# NIP_-3.net
KiCad netlist of a schematic drawn in Altium Designer
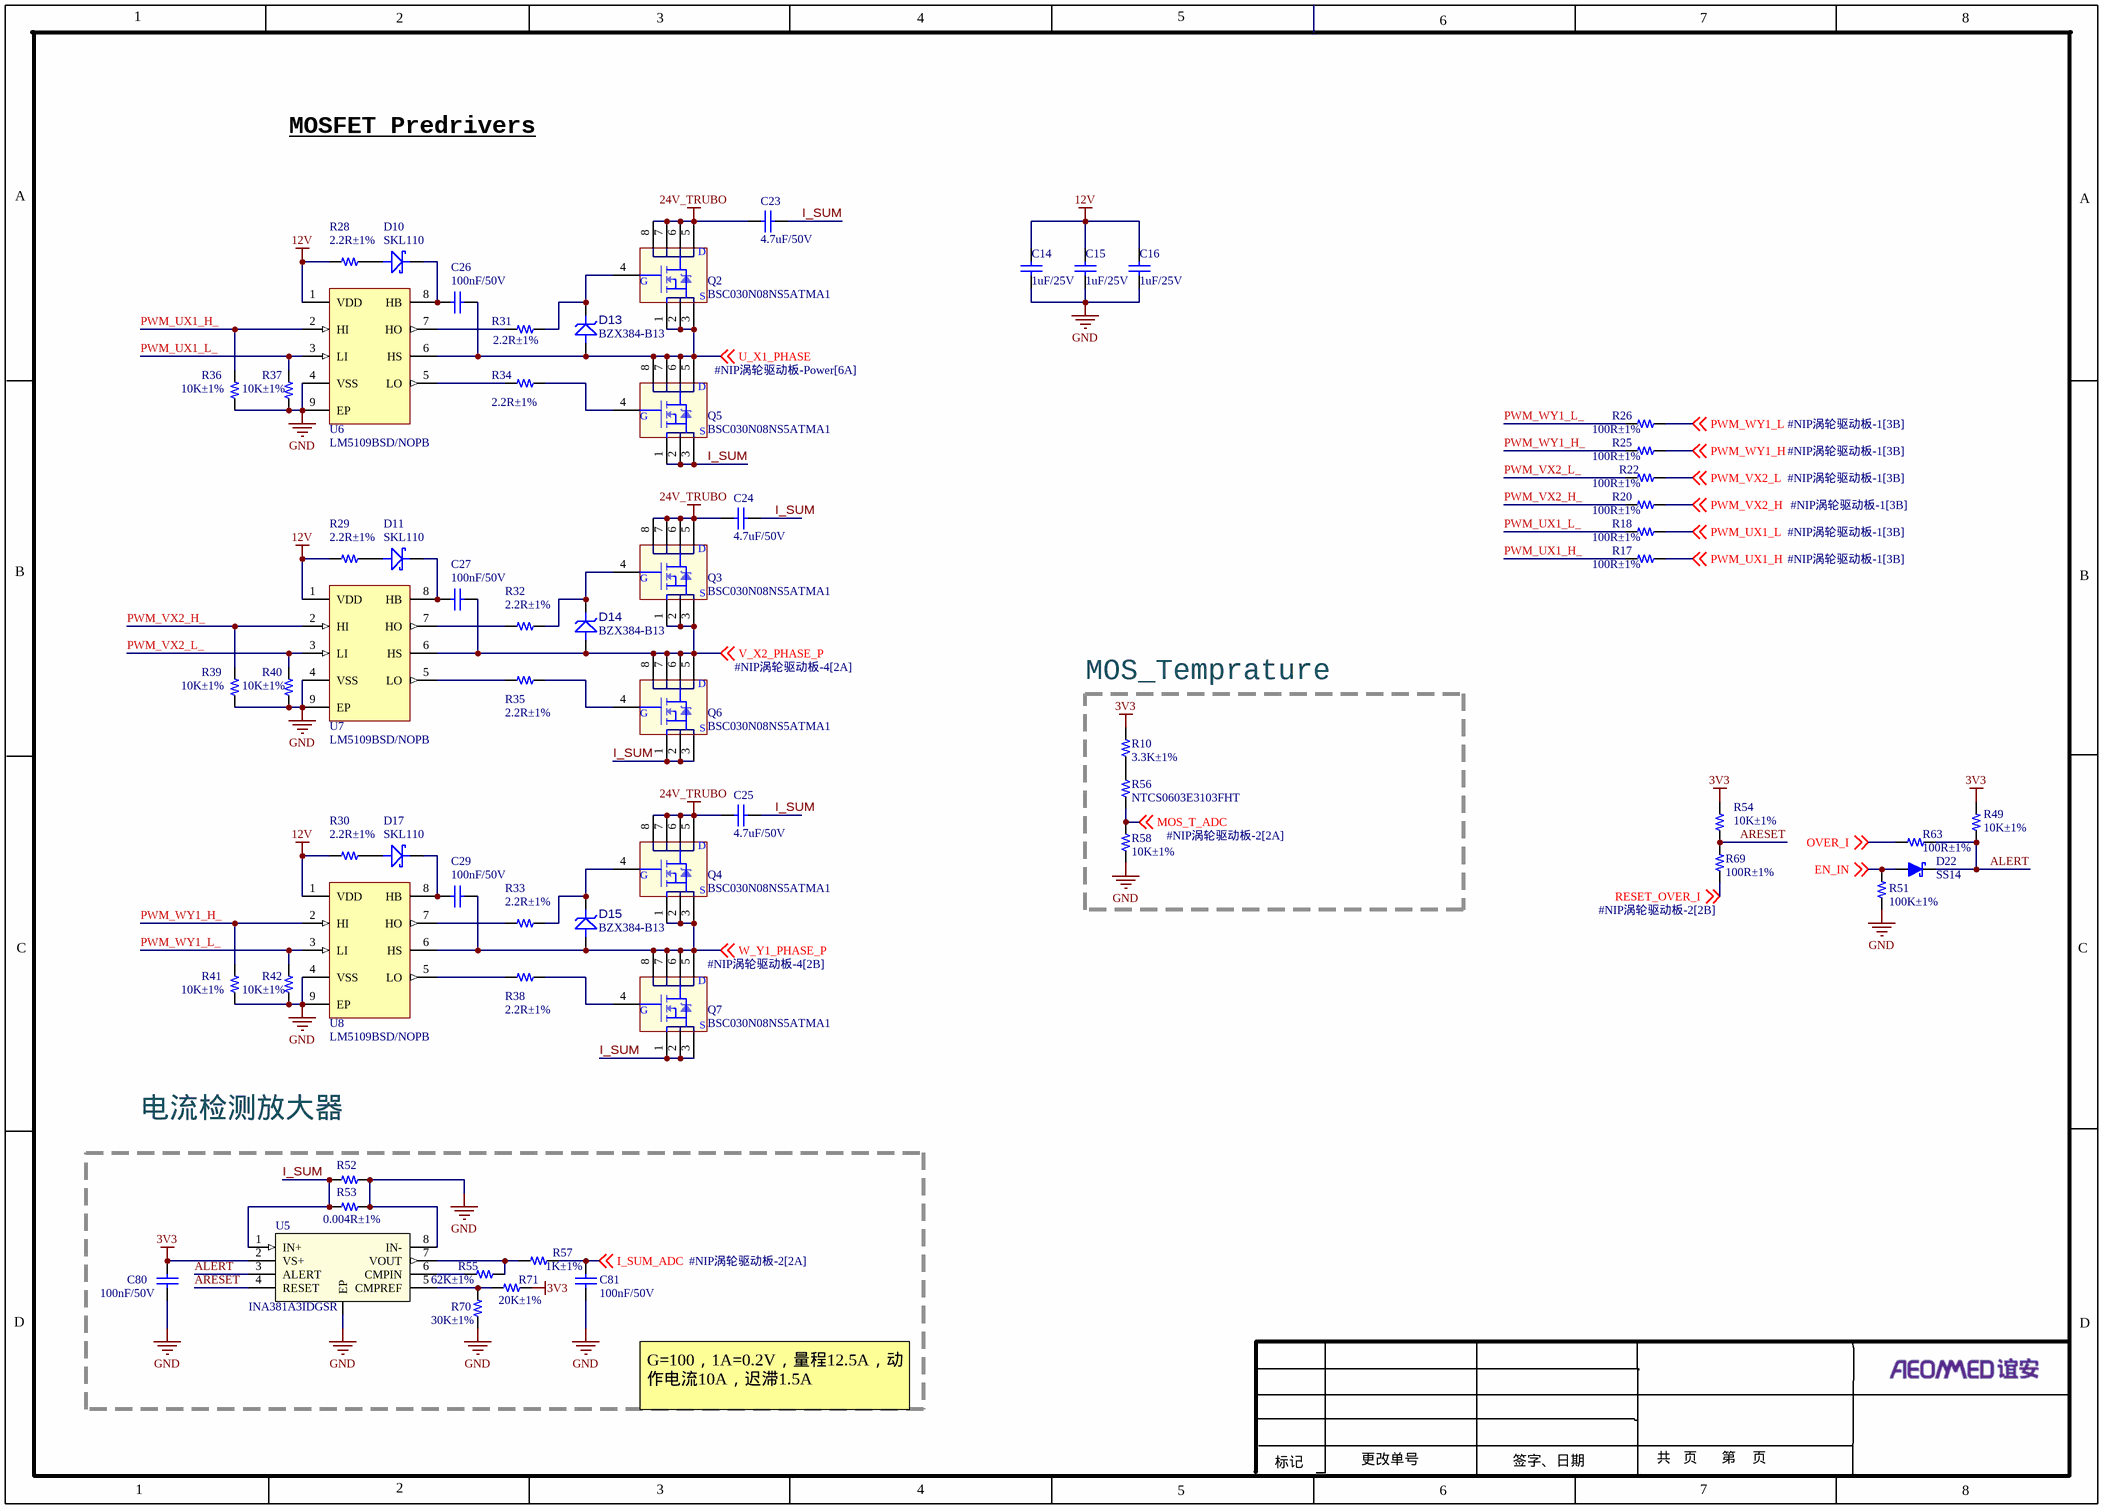
[diagram p0: #NIP涡轮驱动板-3.SchDoc]

(export (version "E")
  (design (tool "Eeschema 10.0.6"))
  (components
    (comp (ref "C14") (value "1uF/25V") (footprint "C-0805") (libsource (lib "Device") (part "C-0805")))
    (comp (ref "C15") (value "1uF/25V") (footprint "C-0805") (libsource (lib "Device") (part "C-0805")))
    (comp (ref "C16") (value "1uF/25V") (footprint "C-0805") (libsource (lib "Device") (part "C-0805")))
    (comp (ref "C23") (value "4.7uF/50V") (footprint "C-1210") (libsource (lib "Device") (part "C-1210")))
    (comp (ref "C24") (value "4.7uF/50V") (footprint "C-1210") (libsource (lib "Device") (part "C-1210")))
    (comp (ref "C25") (value "4.7uF/50V") (footprint "C-1210") (libsource (lib "Device") (part "C-1210")))
    (comp (ref "C26") (value "100nF/50V") (footprint "C-0603") (libsource (lib "Device") (part "C-0603")))
    (comp (ref "C27") (value "100nF/50V") (footprint "C-0603") (libsource (lib "Device") (part "C-0603")))
    (comp (ref "C29") (value "100nF/50V") (footprint "C-0603") (libsource (lib "Device") (part "C-0603")))
    (comp (ref "C80") (value "100nF/50V") (footprint "C0402") (libsource (lib "Device") (part "C-0603")))
    (comp (ref "C81") (value "100nF/50V") (footprint "C0402") (libsource (lib "Device") (part "C-0603")))
    (comp (ref "D10")
      (value "SKL110")
      (footprint "SODFL370X140-2N")
      (description "品牌：DIOTEC，型号：SKL110，1A，100V，ROHS")
      (fields (field (name "MANUFACTURER") "Diotec  Semiconductor"))
      (libsource (lib "altium-import") (part "root_2_DIO-SCHOTTKY_"))
    )
    (comp (ref "D11")
      (value "SKL110")
      (footprint "SODFL370X140-2N")
      (description "品牌：DIOTEC，型号：SKL110，1A，100V，ROHS")
      (fields (field (name "MANUFACTURER") "Diotec  Semiconductor"))
      (libsource (lib "altium-import") (part "root_2_DIO-SCHOTTKY_"))
    )
    (comp (ref "D13")
      (value "BZX384-B13")
      (footprint "SOD2512X100N")
      (description "品牌：NXP，型号：BZX384-B13，13V，SOD-323，ROHS")
      (fields (field (name "MANUFACTURER") "Nexperia"))
      (libsource (lib "BLDC") (part "ZENER"))
    )
    (comp (ref "D14")
      (value "BZX384-B13")
      (footprint "SOD2512X100N")
      (description "品牌：NXP，型号：BZX384-B13，13V，SOD-323，ROHS")
      (fields (field (name "MANUFACTURER") "Nexperia"))
      (libsource (lib "BLDC") (part "ZENER"))
    )
    (comp (ref "D15")
      (value "BZX384-B13")
      (footprint "SOD2512X100N")
      (description "品牌：NXP，型号：BZX384-B13，13V，SOD-323，ROHS")
      (fields (field (name "MANUFACTURER") "Nexperia"))
      (libsource (lib "BLDC") (part "ZENER"))
    )
    (comp (ref "D17")
      (value "SKL110")
      (footprint "SODFL370X140-2N")
      (description "品牌：DIOTEC，型号：SKL110，1A，100V，ROHS")
      (fields (field (name "MANUFACTURER") "Diotec  Semiconductor"))
      (libsource (lib "altium-import") (part "root_2_DIO-SCHOTTKY_"))
    )
    (comp (ref "D22")
      (value "SS14")
      (footprint "DO-214AC/SMA")
      (description "品牌：VISHAY,型号：SS14,1A,40V,ROHS")
      (libsource (lib "Device") (part "Diode- 肖特基-214AC  (SMA)"))
    )
    (comp (ref "Q2")
      (value "BSC030N08NS5ATMA1")
      (footprint "PG-TDSON-8")
      (description "品牌：INFINEON，型号： BSC027N04LSG，40V，100A，ROHS")
      (libsource (lib "IC") (part "BSC027N04LS"))
    )
    (comp (ref "Q3")
      (value "BSC030N08NS5ATMA1")
      (footprint "PG-TDSON-8")
      (description "品牌：INFINEON，型号： BSC027N04LSG，40V，100A，ROHS")
      (libsource (lib "IC") (part "BSC027N04LS"))
    )
    (comp (ref "Q4")
      (value "BSC030N08NS5ATMA1")
      (footprint "PG-TDSON-8")
      (description "品牌：INFINEON，型号： BSC027N04LSG，40V，100A，ROHS")
      (libsource (lib "IC") (part "BSC027N04LS"))
    )
    (comp (ref "Q5")
      (value "BSC030N08NS5ATMA1")
      (footprint "PG-TDSON-8")
      (description "品牌：INFINEON，型号： BSC027N04LSG，40V，100A，ROHS")
      (libsource (lib "IC") (part "BSC027N04LS"))
    )
    (comp (ref "Q6")
      (value "BSC030N08NS5ATMA1")
      (footprint "PG-TDSON-8")
      (description "品牌：INFINEON，型号： BSC027N04LSG，40V，100A，ROHS")
      (libsource (lib "IC") (part "BSC027N04LS"))
    )
    (comp (ref "Q7")
      (value "BSC030N08NS5ATMA1")
      (footprint "PG-TDSON-8")
      (description "品牌：INFINEON，型号： BSC027N04LSG，40V，100A，ROHS")
      (libsource (lib "IC") (part "BSC027N04LS"))
    )
    (comp (ref "R10") (value "3.3K±1%") (footprint "R0402") (libsource (lib "Device") (part "R-0603")))
    (comp (ref "R17") (value "100R±1%") (footprint "R0402") (libsource (lib "Device") (part "R-0603")))
    (comp (ref "R18") (value "100R±1%") (footprint "R0402") (libsource (lib "Device") (part "R-0603")))
    (comp (ref "R20") (value "100R±1%") (footprint "R0402") (libsource (lib "Device") (part "R-0603")))
    (comp (ref "R22") (value "100R±1%") (footprint "R0402") (libsource (lib "Device") (part "R-0603")))
    (comp (ref "R25") (value "100R±1%") (footprint "R0402") (libsource (lib "Device") (part "R-0603")))
    (comp (ref "R26") (value "100R±1%") (footprint "R0402") (libsource (lib "Device") (part "R-0603")))
    (comp (ref "R28") (value "2.2R±1%") (footprint "R-0603") (libsource (lib "Device") (part "R-0603")))
    (comp (ref "R29") (value "2.2R±1%") (footprint "R-0603") (libsource (lib "Device") (part "R-0603")))
    (comp (ref "R30") (value "2.2R±1%") (footprint "R-0603") (libsource (lib "Device") (part "R-0603")))
    (comp (ref "R31") (value "2.2R±1%") (footprint "R-0603") (libsource (lib "Device") (part "R-0603")))
    (comp (ref "R32") (value "2.2R±1%") (footprint "R-0603") (libsource (lib "Device") (part "R-0603")))
    (comp (ref "R33") (value "2.2R±1%") (footprint "R-0603") (libsource (lib "Device") (part "R-0603")))
    (comp (ref "R34") (value "2.2R±1%") (footprint "R-0603") (libsource (lib "Device") (part "R-0603")))
    (comp (ref "R35") (value "2.2R±1%") (footprint "R-0603") (libsource (lib "Device") (part "R-0603")))
    (comp (ref "R36") (value "10K±1%") (footprint "R0402") (libsource (lib "Device") (part "R-0603")))
    (comp (ref "R37") (value "10K±1%") (footprint "R0402") (libsource (lib "Device") (part "R-0603")))
    (comp (ref "R38") (value "2.2R±1%") (footprint "R-0603") (libsource (lib "Device") (part "R-0603")))
    (comp (ref "R39") (value "10K±1%") (footprint "R0402") (libsource (lib "Device") (part "R-0603")))
    (comp (ref "R40") (value "10K±1%") (footprint "R0402") (libsource (lib "Device") (part "R-0603")))
    (comp (ref "R41") (value "10K±1%") (footprint "R0402") (libsource (lib "Device") (part "R-0603")))
    (comp (ref "R42") (value "10K±1%") (footprint "R0402") (libsource (lib "Device") (part "R-0603")))
    (comp (ref "R49") (value "10K±1%") (footprint "R0402") (libsource (lib "Device") (part "R-0603")))
    (comp (ref "R51") (value "100K±1%") (footprint "R0402") (libsource (lib "Device") (part "R-0603")))
    (comp (ref "R52")
      (value "0.004R±1%")
      (footprint "R-2512_4PIN")
      (libsource (lib "Device") (part "R-2512"))
    )
    (comp (ref "R53")
      (value "0.004R±1%")
      (footprint "R-2512_4PIN")
      (libsource (lib "Device") (part "R-2512"))
    )
    (comp (ref "R54") (value "10K±1%") (footprint "R0402") (libsource (lib "Device") (part "R-0603")))
    (comp (ref "R55") (value "62K±1%") (footprint "R0402") (libsource (lib "Device") (part "R-0603")))
    (comp (ref "R56")
      (value "NTCS0603E3103FHT")
      (footprint "R-0603")
      (description "品牌：VISHAY，型号：NTCS0603E3103FHT，10K@25℃, 1%，B=3960,ROHS")
      (libsource (lib "Device") (part "R-0603"))
    )
    (comp (ref "R57") (value "1K±1%") (footprint "R0402") (libsource (lib "Device") (part "R-0603")))
    (comp (ref "R58") (value "10K±1%") (footprint "R0402") (libsource (lib "Device") (part "R-0603")))
    (comp (ref "R63") (value "100R±1%") (footprint "R0402") (libsource (lib "Device") (part "R-0603")))
    (comp (ref "R69") (value "100R±1%") (footprint "R0402") (libsource (lib "Device") (part "R-0603")))
    (comp (ref "R70") (value "30K±1%") (footprint "R0402") (libsource (lib "Device") (part "R-0603")))
    (comp (ref "R71") (value "20K±1%") (footprint "R0402") (libsource (lib "Device") (part "R-0603")))
    (comp (ref "U5")
      (value "INA381A3IDGSR")
      (footprint "WSON-8_L2.0-W2.0-P0.50-BL-EP0.9")
      (description "品牌：TI，型号：INA381A1IDGSR，ROHS")
      (fields (field (name "COPYRIGHT") "Copyright (C) 2022 Ultra Librarian. All rights reserved."))
      (libsource (lib "all") (part "INA381A2IDSGR"))
    )
    (comp (ref "U6")
      (value "LM5109BSD/NOPB")
      (footprint "PSON80P400X80_HS-9N")
      (description "品牌：TI，型号：LM5109BSD/NOPB，ROHS")
      (fields (field (name "MANUFACTURER") "Texas Instruments"))
      (libsource (lib "BLDC") (part "LM5109"))
    )
    (comp (ref "U7")
      (value "LM5109BSD/NOPB")
      (footprint "PSON80P400X80_HS-9N")
      (description "品牌：TI，型号：LM5109BSD/NOPB，ROHS")
      (fields (field (name "MANUFACTURER") "Texas Instruments"))
      (libsource (lib "BLDC") (part "LM5109"))
    )
    (comp (ref "U8")
      (value "LM5109BSD/NOPB")
      (footprint "PSON80P400X80_HS-9N")
      (description "品牌：TI，型号：LM5109BSD/NOPB，ROHS")
      (fields (field (name "MANUFACTURER") "Texas Instruments"))
      (libsource (lib "BLDC") (part "LM5109"))
    )
  )
  (nets
    (net (code "1") (name "/ALERT") (class "Default")
      (node (ref "D22") (pin "K") (pinfunction "K_K") (pintype "passive"))
      (node (ref "R49") (pin "2") (pinfunction "2_2") (pintype "passive"))
      (node (ref "R63") (pin "1") (pinfunction "1_1") (pintype "passive"))
      (node (ref "U5") (pin "3") (pinfunction "ALERT_3") (pintype "passive"))
    )
    (net (code "2") (name "/ARESET") (class "Default")
      (node (ref "R54") (pin "2") (pinfunction "2_2") (pintype "passive"))
      (node (ref "R69") (pin "1") (pinfunction "1_1") (pintype "passive"))
      (node (ref "U5") (pin "4") (pinfunction "RESET_4") (pintype "passive"))
    )
    (net (code "3") (name "/I_SUM") (class "Default")
      (node (ref "C23") (pin "1") (pinfunction "1_1") (pintype "passive"))
      (node (ref "C24") (pin "1") (pinfunction "1_1") (pintype "passive"))
      (node (ref "C25") (pin "1") (pinfunction "1_1") (pintype "passive"))
      (node (ref "Q5") (pin "1") (pinfunction "S_1") (pintype "passive"))
      (node (ref "Q5") (pin "2") (pinfunction "S_2") (pintype "passive"))
      (node (ref "Q5") (pin "3") (pinfunction "S_3") (pintype "passive"))
      (node (ref "Q6") (pin "1") (pinfunction "S_1") (pintype "passive"))
      (node (ref "Q6") (pin "2") (pinfunction "S_2") (pintype "passive"))
      (node (ref "Q6") (pin "3") (pinfunction "S_3") (pintype "passive"))
      (node (ref "Q7") (pin "1") (pinfunction "S_1") (pintype "passive"))
      (node (ref "Q7") (pin "2") (pinfunction "S_2") (pintype "passive"))
      (node (ref "Q7") (pin "3") (pinfunction "S_3") (pintype "passive"))
      (node (ref "R52") (pin "2") (pinfunction "2_2") (pintype "passive"))
      (node (ref "R53") (pin "2") (pinfunction "2_2") (pintype "passive"))
      (node (ref "U5") (pin "1") (pinfunction "IN+_1") (pintype "input"))
    )
    (net (code "4") (name "/PWM_UX1_H_") (class "Default")
      (node (ref "R17") (pin "1") (pinfunction "1_1") (pintype "passive"))
      (node (ref "R36") (pin "2") (pinfunction "2_2") (pintype "passive"))
      (node (ref "U6") (pin "2") (pinfunction "HI_2") (pintype "input"))
    )
    (net (code "5") (name "/PWM_UX1_L_") (class "Default")
      (node (ref "R18") (pin "1") (pinfunction "1_1") (pintype "passive"))
      (node (ref "R37") (pin "2") (pinfunction "2_2") (pintype "passive"))
      (node (ref "U6") (pin "3") (pinfunction "LI_3") (pintype "input"))
    )
    (net (code "6") (name "/PWM_VX2_H_") (class "Default")
      (node (ref "R20") (pin "1") (pinfunction "1_1") (pintype "passive"))
      (node (ref "R39") (pin "2") (pinfunction "2_2") (pintype "passive"))
      (node (ref "U7") (pin "2") (pinfunction "HI_2") (pintype "input"))
    )
    (net (code "7") (name "/PWM_VX2_L_") (class "Default")
      (node (ref "R22") (pin "1") (pinfunction "1_1") (pintype "passive"))
      (node (ref "R40") (pin "2") (pinfunction "2_2") (pintype "passive"))
      (node (ref "U7") (pin "3") (pinfunction "LI_3") (pintype "input"))
    )
    (net (code "8") (name "/PWM_WY1_H_") (class "Default")
      (node (ref "R25") (pin "1") (pinfunction "1_1") (pintype "passive"))
      (node (ref "R41") (pin "2") (pinfunction "2_2") (pintype "passive"))
      (node (ref "U8") (pin "2") (pinfunction "HI_2") (pintype "input"))
    )
    (net (code "9") (name "/PWM_WY1_L_") (class "Default")
      (node (ref "R26") (pin "1") (pinfunction "1_1") (pintype "passive"))
      (node (ref "R42") (pin "2") (pinfunction "2_2") (pintype "passive"))
      (node (ref "U8") (pin "3") (pinfunction "LI_3") (pintype "input"))
    )
    (net (code "10") (name "3V3") (class "Default")
      (node (ref "C80") (pin "2") (pinfunction "2_2") (pintype "passive"))
      (node (ref "R10") (pin "2") (pinfunction "2_2") (pintype "passive"))
      (node (ref "R49") (pin "1") (pinfunction "1_1") (pintype "passive"))
      (node (ref "R54") (pin "1") (pinfunction "1_1") (pintype "passive"))
      (node (ref "R71") (pin "2") (pinfunction "2_2") (pintype "passive"))
      (node (ref "U5") (pin "2") (pinfunction "VS+_2") (pintype "passive"))
    )
    (net (code "11") (name "12V") (class "Default")
      (node (ref "C14") (pin "2") (pinfunction "2_2") (pintype "passive"))
      (node (ref "C15") (pin "2") (pinfunction "2_2") (pintype "passive"))
      (node (ref "C16") (pin "2") (pinfunction "2_2") (pintype "passive"))
      (node (ref "R28") (pin "2") (pinfunction "2_2") (pintype "passive"))
      (node (ref "R29") (pin "2") (pinfunction "2_2") (pintype "passive"))
      (node (ref "R30") (pin "2") (pinfunction "2_2") (pintype "passive"))
      (node (ref "U6") (pin "1") (pinfunction "VDD_1") (pintype "power_in"))
      (node (ref "U7") (pin "1") (pinfunction "VDD_1") (pintype "power_in"))
      (node (ref "U8") (pin "1") (pinfunction "VDD_1") (pintype "power_in"))
    )
    (net (code "12") (name "24V_TRUBO") (class "Default")
      (node (ref "C23") (pin "2") (pinfunction "2_2") (pintype "passive"))
      (node (ref "C24") (pin "2") (pinfunction "2_2") (pintype "passive"))
      (node (ref "C25") (pin "2") (pinfunction "2_2") (pintype "passive"))
      (node (ref "Q2") (pin "5") (pinfunction "D_5") (pintype "passive"))
      (node (ref "Q2") (pin "6") (pinfunction "D_6") (pintype "passive"))
      (node (ref "Q2") (pin "7") (pinfunction "D_7") (pintype "passive"))
      (node (ref "Q2") (pin "8") (pinfunction "D_8") (pintype "passive"))
      (node (ref "Q3") (pin "5") (pinfunction "D_5") (pintype "passive"))
      (node (ref "Q3") (pin "6") (pinfunction "D_6") (pintype "passive"))
      (node (ref "Q3") (pin "7") (pinfunction "D_7") (pintype "passive"))
      (node (ref "Q3") (pin "8") (pinfunction "D_8") (pintype "passive"))
      (node (ref "Q4") (pin "5") (pinfunction "D_5") (pintype "passive"))
      (node (ref "Q4") (pin "6") (pinfunction "D_6") (pintype "passive"))
      (node (ref "Q4") (pin "7") (pinfunction "D_7") (pintype "passive"))
      (node (ref "Q4") (pin "8") (pinfunction "D_8") (pintype "passive"))
    )
    (net (code "13") (name "EN_IN") (class "Default")
      (node (ref "D22") (pin "A") (pinfunction "A_A") (pintype "passive"))
      (node (ref "R51") (pin "1") (pinfunction "1_1") (pintype "passive"))
    )
    (net (code "14") (name "GND") (class "Default")
      (node (ref "C14") (pin "1") (pinfunction "1_1") (pintype "passive"))
      (node (ref "C15") (pin "1") (pinfunction "1_1") (pintype "passive"))
      (node (ref "C16") (pin "1") (pinfunction "1_1") (pintype "passive"))
      (node (ref "C80") (pin "1") (pinfunction "1_1") (pintype "passive"))
      (node (ref "C81") (pin "1") (pinfunction "1_1") (pintype "passive"))
      (node (ref "R36") (pin "1") (pinfunction "1_1") (pintype "passive"))
      (node (ref "R37") (pin "1") (pinfunction "1_1") (pintype "passive"))
      (node (ref "R39") (pin "1") (pinfunction "1_1") (pintype "passive"))
      (node (ref "R40") (pin "1") (pinfunction "1_1") (pintype "passive"))
      (node (ref "R41") (pin "1") (pinfunction "1_1") (pintype "passive"))
      (node (ref "R42") (pin "1") (pinfunction "1_1") (pintype "passive"))
      (node (ref "R51") (pin "2") (pinfunction "2_2") (pintype "passive"))
      (node (ref "R52") (pin "1") (pinfunction "1_1") (pintype "passive"))
      (node (ref "R53") (pin "1") (pinfunction "1_1") (pintype "passive"))
      (node (ref "R58") (pin "1") (pinfunction "1_1") (pintype "passive"))
      (node (ref "R70") (pin "1") (pinfunction "1_1") (pintype "passive"))
      (node (ref "U5") (pin "8") (pinfunction "IN-_8") (pintype "passive"))
      (node (ref "U5") (pin "9") (pinfunction "EP_9") (pintype "passive"))
      (node (ref "U6") (pin "4") (pinfunction "VSS_4") (pintype "power_in"))
      (node (ref "U6") (pin "9") (pinfunction "EP_9") (pintype "passive"))
      (node (ref "U7") (pin "4") (pinfunction "VSS_4") (pintype "power_in"))
      (node (ref "U7") (pin "9") (pinfunction "EP_9") (pintype "passive"))
      (node (ref "U8") (pin "4") (pinfunction "VSS_4") (pintype "power_in"))
      (node (ref "U8") (pin "9") (pinfunction "EP_9") (pintype "passive"))
    )
    (net (code "15") (name "I_SUM_ADC") (class "Default")
      (node (ref "C81") (pin "2") (pinfunction "2_2") (pintype "passive"))
      (node (ref "R57") (pin "2") (pinfunction "2_2") (pintype "passive"))
    )
    (net (code "16") (name "MOS_T_ADC") (class "Default")
      (node (ref "R56") (pin "1") (pinfunction "1_1") (pintype "passive"))
      (node (ref "R58") (pin "2") (pinfunction "2_2") (pintype "passive"))
    )
    (net (code "17") (name "Net-(D10-Pad2)") (class "Default")
      (node (ref "D10") (pin "2") (pinfunction "2_2") (pintype "passive"))
      (node (ref "R28") (pin "1") (pinfunction "1_1") (pintype "passive"))
    )
    (net (code "18") (name "Net-(D11-Pad2)") (class "Default")
      (node (ref "D11") (pin "2") (pinfunction "2_2") (pintype "passive"))
      (node (ref "R29") (pin "1") (pinfunction "1_1") (pintype "passive"))
    )
    (net (code "19") (name "Net-(D13-K)") (class "Default")
      (node (ref "D13") (pin "1") (pinfunction "K_1") (pintype "passive"))
      (node (ref "Q2") (pin "4") (pinfunction "G_4") (pintype "passive"))
      (node (ref "R31") (pin "1") (pinfunction "1_1") (pintype "passive"))
    )
    (net (code "20") (name "Net-(D14-K)") (class "Default")
      (node (ref "D14") (pin "1") (pinfunction "K_1") (pintype "passive"))
      (node (ref "Q3") (pin "4") (pinfunction "G_4") (pintype "passive"))
      (node (ref "R32") (pin "1") (pinfunction "1_1") (pintype "passive"))
    )
    (net (code "21") (name "Net-(D15-K)") (class "Default")
      (node (ref "D15") (pin "1") (pinfunction "K_1") (pintype "passive"))
      (node (ref "Q4") (pin "4") (pinfunction "G_4") (pintype "passive"))
      (node (ref "R33") (pin "1") (pinfunction "1_1") (pintype "passive"))
    )
    (net (code "22") (name "Net-(D17-Pad2)") (class "Default")
      (node (ref "D17") (pin "2") (pinfunction "2_2") (pintype "passive"))
      (node (ref "R30") (pin "1") (pinfunction "1_1") (pintype "passive"))
    )
    (net (code "23") (name "Net-(Q5-G)") (class "Default")
      (node (ref "Q5") (pin "4") (pinfunction "G_4") (pintype "passive"))
      (node (ref "R34") (pin "1") (pinfunction "1_1") (pintype "passive"))
    )
    (net (code "24") (name "Net-(Q6-G)") (class "Default")
      (node (ref "Q6") (pin "4") (pinfunction "G_4") (pintype "passive"))
      (node (ref "R35") (pin "1") (pinfunction "1_1") (pintype "passive"))
    )
    (net (code "25") (name "Net-(Q7-G)") (class "Default")
      (node (ref "Q7") (pin "4") (pinfunction "G_4") (pintype "passive"))
      (node (ref "R38") (pin "1") (pinfunction "1_1") (pintype "passive"))
    )
    (net (code "26") (name "Net-(R10-Pad1)") (class "Default")
      (node (ref "R10") (pin "1") (pinfunction "1_1") (pintype "passive"))
      (node (ref "R56") (pin "2") (pinfunction "2_2") (pintype "passive"))
    )
    (net (code "27") (name "Net-(U5-CMPIN)") (class "Default")
      (node (ref "R55") (pin "1") (pinfunction "1_1") (pintype "passive"))
      (node (ref "U5") (pin "6") (pinfunction "CMPIN_6") (pintype "passive"))
    )
    (net (code "28") (name "Net-(U5-CMPREF)") (class "Default")
      (node (ref "R70") (pin "2") (pinfunction "2_2") (pintype "passive"))
      (node (ref "R71") (pin "1") (pinfunction "1_1") (pintype "passive"))
      (node (ref "U5") (pin "5") (pinfunction "CMPREF_5") (pintype "passive"))
    )
    (net (code "29") (name "Net-(U5-VOUT)") (class "Default")
      (node (ref "R55") (pin "2") (pinfunction "2_2") (pintype "passive"))
      (node (ref "R57") (pin "1") (pinfunction "1_1") (pintype "passive"))
      (node (ref "U5") (pin "7") (pinfunction "VOUT_7") (pintype "output"))
    )
    (net (code "30") (name "Net-(U6-HB)") (class "Default")
      (node (ref "C26") (pin "2") (pinfunction "2_2") (pintype "passive"))
      (node (ref "D10") (pin "1") (pinfunction "1_1") (pintype "passive"))
      (node (ref "U6") (pin "8") (pinfunction "HB_8") (pintype "power_in"))
    )
    (net (code "31") (name "Net-(U6-HO)") (class "Default")
      (node (ref "R31") (pin "2") (pinfunction "2_2") (pintype "passive"))
      (node (ref "U6") (pin "7") (pinfunction "HO_7") (pintype "output"))
    )
    (net (code "32") (name "Net-(U6-LO)") (class "Default")
      (node (ref "R34") (pin "2") (pinfunction "2_2") (pintype "passive"))
      (node (ref "U6") (pin "5") (pinfunction "LO_5") (pintype "output"))
    )
    (net (code "33") (name "Net-(U7-HB)") (class "Default")
      (node (ref "C27") (pin "2") (pinfunction "2_2") (pintype "passive"))
      (node (ref "D11") (pin "1") (pinfunction "1_1") (pintype "passive"))
      (node (ref "U7") (pin "8") (pinfunction "HB_8") (pintype "power_in"))
    )
    (net (code "34") (name "Net-(U7-HO)") (class "Default")
      (node (ref "R32") (pin "2") (pinfunction "2_2") (pintype "passive"))
      (node (ref "U7") (pin "7") (pinfunction "HO_7") (pintype "output"))
    )
    (net (code "35") (name "Net-(U7-LO)") (class "Default")
      (node (ref "R35") (pin "2") (pinfunction "2_2") (pintype "passive"))
      (node (ref "U7") (pin "5") (pinfunction "LO_5") (pintype "output"))
    )
    (net (code "36") (name "Net-(U8-HB)") (class "Default")
      (node (ref "C29") (pin "2") (pinfunction "2_2") (pintype "passive"))
      (node (ref "D17") (pin "1") (pinfunction "1_1") (pintype "passive"))
      (node (ref "U8") (pin "8") (pinfunction "HB_8") (pintype "power_in"))
    )
    (net (code "37") (name "Net-(U8-HO)") (class "Default")
      (node (ref "R33") (pin "2") (pinfunction "2_2") (pintype "passive"))
      (node (ref "U8") (pin "7") (pinfunction "HO_7") (pintype "output"))
    )
    (net (code "38") (name "Net-(U8-LO)") (class "Default")
      (node (ref "R38") (pin "2") (pinfunction "2_2") (pintype "passive"))
      (node (ref "U8") (pin "5") (pinfunction "LO_5") (pintype "output"))
    )
    (net (code "39") (name "OVER_I") (class "Default")
      (node (ref "R63") (pin "2") (pinfunction "2_2") (pintype "passive"))
    )
    (net (code "40") (name "PWM_UX1_H") (class "Default")
      (node (ref "R17") (pin "2") (pinfunction "2_2") (pintype "passive"))
    )
    (net (code "41") (name "PWM_UX1_L") (class "Default")
      (node (ref "R18") (pin "2") (pinfunction "2_2") (pintype "passive"))
    )
    (net (code "42") (name "PWM_VX2_H") (class "Default")
      (node (ref "R20") (pin "2") (pinfunction "2_2") (pintype "passive"))
    )
    (net (code "43") (name "PWM_VX2_L") (class "Default")
      (node (ref "R22") (pin "2") (pinfunction "2_2") (pintype "passive"))
    )
    (net (code "44") (name "PWM_WY1_H") (class "Default")
      (node (ref "R25") (pin "2") (pinfunction "2_2") (pintype "passive"))
    )
    (net (code "45") (name "PWM_WY1_L") (class "Default")
      (node (ref "R26") (pin "2") (pinfunction "2_2") (pintype "passive"))
    )
    (net (code "46") (name "RESET_OVER_I") (class "Default")
      (node (ref "R69") (pin "2") (pinfunction "2_2") (pintype "passive"))
    )
    (net (code "47") (name "U_X1_PHASE") (class "Default")
      (node (ref "C26") (pin "1") (pinfunction "1_1") (pintype "passive"))
      (node (ref "D13") (pin "2") (pinfunction "A_2") (pintype "passive"))
      (node (ref "Q2") (pin "1") (pinfunction "S_1") (pintype "passive"))
      (node (ref "Q2") (pin "2") (pinfunction "S_2") (pintype "passive"))
      (node (ref "Q2") (pin "3") (pinfunction "S_3") (pintype "passive"))
      (node (ref "Q5") (pin "5") (pinfunction "D_5") (pintype "passive"))
      (node (ref "Q5") (pin "6") (pinfunction "D_6") (pintype "passive"))
      (node (ref "Q5") (pin "7") (pinfunction "D_7") (pintype "passive"))
      (node (ref "Q5") (pin "8") (pinfunction "D_8") (pintype "passive"))
      (node (ref "U6") (pin "6") (pinfunction "HS_6") (pintype "passive"))
    )
    (net (code "48") (name "V_X2_PHASE_P") (class "Default")
      (node (ref "C27") (pin "1") (pinfunction "1_1") (pintype "passive"))
      (node (ref "D14") (pin "2") (pinfunction "A_2") (pintype "passive"))
      (node (ref "Q3") (pin "1") (pinfunction "S_1") (pintype "passive"))
      (node (ref "Q3") (pin "2") (pinfunction "S_2") (pintype "passive"))
      (node (ref "Q3") (pin "3") (pinfunction "S_3") (pintype "passive"))
      (node (ref "Q6") (pin "5") (pinfunction "D_5") (pintype "passive"))
      (node (ref "Q6") (pin "6") (pinfunction "D_6") (pintype "passive"))
      (node (ref "Q6") (pin "7") (pinfunction "D_7") (pintype "passive"))
      (node (ref "Q6") (pin "8") (pinfunction "D_8") (pintype "passive"))
      (node (ref "U7") (pin "6") (pinfunction "HS_6") (pintype "passive"))
    )
    (net (code "49") (name "W_Y1_PHASE_P") (class "Default")
      (node (ref "C29") (pin "1") (pinfunction "1_1") (pintype "passive"))
      (node (ref "D15") (pin "2") (pinfunction "A_2") (pintype "passive"))
      (node (ref "Q4") (pin "1") (pinfunction "S_1") (pintype "passive"))
      (node (ref "Q4") (pin "2") (pinfunction "S_2") (pintype "passive"))
      (node (ref "Q4") (pin "3") (pinfunction "S_3") (pintype "passive"))
      (node (ref "Q7") (pin "5") (pinfunction "D_5") (pintype "passive"))
      (node (ref "Q7") (pin "6") (pinfunction "D_6") (pintype "passive"))
      (node (ref "Q7") (pin "7") (pinfunction "D_7") (pintype "passive"))
      (node (ref "Q7") (pin "8") (pinfunction "D_8") (pintype "passive"))
      (node (ref "U8") (pin "6") (pinfunction "HS_6") (pintype "passive"))
    )
  )
)
